# half-bridge.net
KiCad netlist of a schematic drawn in Altium Designer
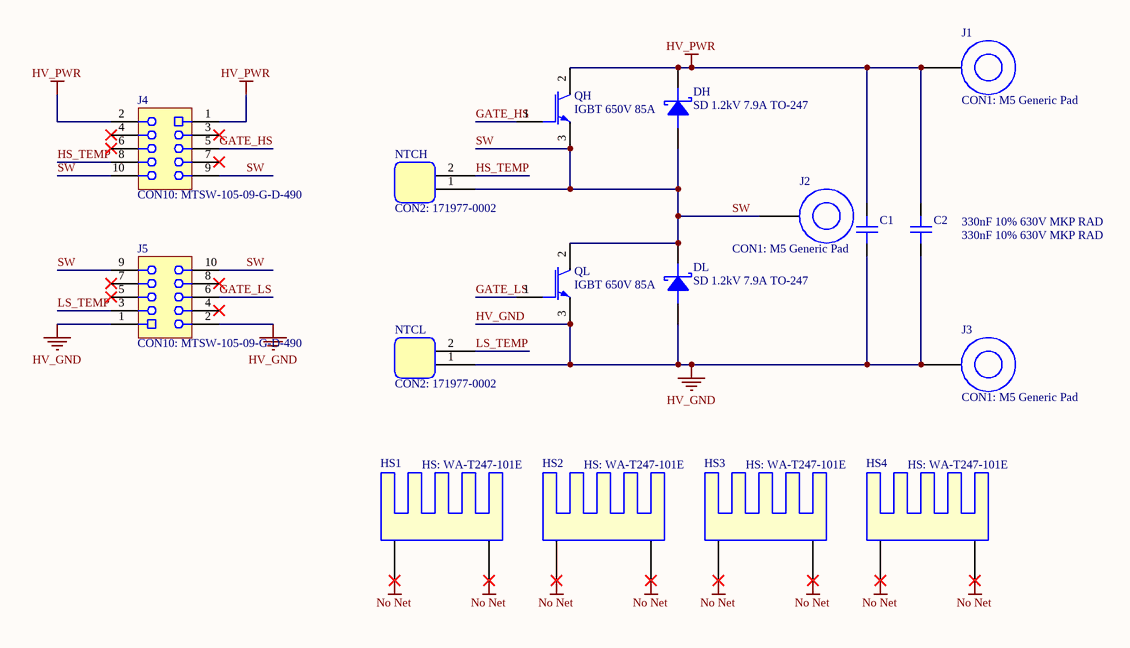
[diagram p0: half-bridge.SchDoc]

(export (version "E")
  (design (tool "Eeschema 10.0.6"))
  (components
    (comp (ref "C1")
      (value "330nF 10% 630V MKP RAD")
      (footprint "330nF 10% 630V MKP RAD-Footprint-1")
      (description "Film Capacitor, Polypropylene, 630V, 10% +Tol, 10% -Tol, 0.33uF, Through Hole Mount")
      (fields (field (name "MANUFACTURER PART NUMBER") "R71PI333050H6K"))
      (libsource (lib "EMEA- E-Tech Racing- I'Escola d'Enginyeria de Barcelona Est") (part "330nF 10% 630V MKP RAD"))
    )
    (comp (ref "C2")
      (value "330nF 10% 630V MKP RAD")
      (footprint "330nF 10% 630V MKP RAD-Footprint-1")
      (description "Film Capacitor, Polypropylene, 630V, 10% +Tol, 10% -Tol, 0.33uF, Through Hole Mount")
      (fields (field (name "MANUFACTURER PART NUMBER") "R71PI333050H6K"))
      (libsource (lib "EMEA- E-Tech Racing- I'Escola d'Enginyeria de Barcelona Est") (part "330nF 10% 630V MKP RAD"))
    )
    (comp (ref "DH")
      (value "SD 1.2kV 7.9A TO-247")
      (footprint "SSTO247-3-NCT")
      (description "L-series Gallium Oxide Schottky barrier diode from Novel Crystal Technology")
      (fields
        (field (name "MANUFACTURER PART NUMBER") "NCT-L")
        (field (name "MANUFACTURER") "Novel Crystal Technology")
      )
      (libsource (lib "EMEA- E-Tech Racing- I'Escola d'Enginyeria de Barcelona Est") (part "SD 1.2kV 7.9A TO-247"))
    )
    (comp (ref "DL")
      (value "SD 1.2kV 7.9A TO-247")
      (footprint "SSTO247-3-NCT")
      (description "L-series Gallium Oxide Schottky barrier diode from Novel Crystal Technology")
      (fields
        (field (name "MANUFACTURER PART NUMBER") "NCT-L")
        (field (name "MANUFACTURER") "Novel Crystal Technology")
      )
      (libsource (lib "EMEA- E-Tech Racing- I'Escola d'Enginyeria de Barcelona Est") (part "SD 1.2kV 7.9A TO-247"))
    )
    (comp (ref "HS1")
      (value "HS: WA-T247-101E")
      (footprint "FP-WA-T247-101E-MFG")
      (description "Heatsink, TEH100 Restr Series, TEH70 Restr Series, TO-247, 11C/W, 43.4X23.4X32MM")
      (fields (field (name "MANUFACTURER PART NUMBER") "WA-T247-101E"))
      (libsource (lib "EMEA- E-Tech Racing- I'Escola d'Enginyeria de Barcelona Est") (part "HS{colon}  OMNI-UNI-30-25-D-Symbol-1"))
    )
    (comp (ref "HS2")
      (value "HS: WA-T247-101E")
      (footprint "FP-WA-T247-101E-MFG")
      (description "Heatsink, TEH100 Restr Series, TEH70 Restr Series, TO-247, 11C/W, 43.4X23.4X32MM")
      (fields (field (name "MANUFACTURER PART NUMBER") "WA-T247-101E"))
      (libsource (lib "EMEA- E-Tech Racing- I'Escola d'Enginyeria de Barcelona Est") (part "HS{colon}  OMNI-UNI-30-25-D-Symbol-1"))
    )
    (comp (ref "HS3")
      (value "HS: WA-T247-101E")
      (footprint "FP-WA-T247-101E-MFG")
      (description "Heatsink, TEH100 Restr Series, TEH70 Restr Series, TO-247, 11C/W, 43.4X23.4X32MM")
      (fields (field (name "MANUFACTURER PART NUMBER") "WA-T247-101E"))
      (libsource (lib "EMEA- E-Tech Racing- I'Escola d'Enginyeria de Barcelona Est") (part "HS{colon}  OMNI-UNI-30-25-D-Symbol-1"))
    )
    (comp (ref "HS4")
      (value "HS: WA-T247-101E")
      (footprint "FP-WA-T247-101E-MFG")
      (description "Heatsink, TEH100 Restr Series, TEH70 Restr Series, TO-247, 11C/W, 43.4X23.4X32MM")
      (fields (field (name "MANUFACTURER PART NUMBER") "WA-T247-101E"))
      (libsource (lib "EMEA- E-Tech Racing- I'Escola d'Enginyeria de Barcelona Est") (part "HS{colon}  OMNI-UNI-30-25-D-Symbol-1"))
    )
    (comp (ref "J1")
      (value "CON1: M5 Generic Pad")
      (footprint "CON1: M5 Generic Pad-Footprint-1")
      (description "Generic M5 connector for power or mounting")
      (libsource (lib "EMEA- E-Tech Racing- I'Escola d'Enginyeria de Barcelona Est") (part "CON1{colon} M5 Generic Pad-Symbol-1"))
    )
    (comp (ref "J2")
      (value "CON1: M5 Generic Pad")
      (footprint "CON1: M5 Generic Pad-Footprint-1")
      (description "Generic M5 connector for power or mounting")
      (libsource (lib "EMEA- E-Tech Racing- I'Escola d'Enginyeria de Barcelona Est") (part "CON1{colon} M5 Generic Pad-Symbol-1"))
    )
    (comp (ref "J3")
      (value "CON1: M5 Generic Pad")
      (footprint "CON1: M5 Generic Pad-Footprint-1")
      (description "Generic M5 connector for power or mounting")
      (libsource (lib "EMEA- E-Tech Racing- I'Escola d'Enginyeria de Barcelona Est") (part "CON1{colon} M5 Generic Pad-Symbol-1"))
    )
    (comp (ref "J4")
      (value "CON10: MTSW-105-09-G-D-490")
      (footprint "MTSW-105-09-G-D-490")
      (description "Pin Header, Board-to-Board, 2.54 mm, 2 Rows, 10 Contacts, Through Hole, MTSW Series")
      (libsource (lib "EMEA- E-Tech Racing- I'Escola d'Enginyeria de Barcelona Est") (part "CN-2P-F-R10"))
    )
    (comp (ref "J5")
      (value "CON10: MTSW-105-09-G-D-490")
      (footprint "MTSW-105-09-G-D-490")
      (description "Pin Header, Board-to-Board, 2.54 mm, 2 Rows, 10 Contacts, Through Hole, MTSW Series")
      (libsource (lib "") (part "CN-2P-F-R10_1"))
    )
    (comp (ref "NTCH")
      (value "CON2: 171977-0002")
      (footprint "CON2: 171977-0002-Footprint-1")
      (fields (field (name "MANUFACTURER PART NUMBER") "171977-0002") (field (name "MANUFACTURER") "Molex"))
      (libsource (lib "EMEA- E-Tech Racing- I'Escola d'Enginyeria de Barcelona Est") (part "CON2{colon} 171977-0002-Symbol-1"))
    )
    (comp (ref "NTCL")
      (value "CON2: 171977-0002")
      (footprint "CON2: 171977-0002-Footprint-1")
      (fields (field (name "MANUFACTURER PART NUMBER") "171977-0002") (field (name "MANUFACTURER") "Molex"))
      (libsource (lib "EMEA- E-Tech Racing- I'Escola d'Enginyeria de Barcelona Est") (part "CON2{colon} 171977-0002-Symbol-1"))
    )
    (comp (ref "QH")
      (value "IGBT 650V 85A")
      (footprint "TO247P159X260-3")
      (description "650V, 85A, TO-247-3 Low VCE(sat) IGBT in TRENCHSTOP 5 technology")
      (fields
        (field (name "MANUFACTURER") "Infineon")
        (field (name "MANUFACTURER PART NUMBER") "IGW30N65L5XKSA1")
      )
      (libsource (lib "EMEA- E-Tech Racing- I'Escola d'Enginyeria de Barcelona Est") (part "IGBT 650V 85A"))
    )
    (comp (ref "QL")
      (value "IGBT 650V 85A")
      (footprint "TO247P159X260-3")
      (description "650V, 85A, TO-247-3 Low VCE(sat) IGBT in TRENCHSTOP 5 technology")
      (fields
        (field (name "MANUFACTURER") "Infineon")
        (field (name "MANUFACTURER PART NUMBER") "IGW30N65L5XKSA1")
      )
      (libsource (lib "EMEA- E-Tech Racing- I'Escola d'Enginyeria de Barcelona Est") (part "IGBT 650V 85A"))
    )
  )
  (nets
    (net (code "1") (name "/GATE_HS") (class "Default")
      (node (ref "J4") (pin "5") (pinfunction "5_5") (pintype "passive"))
      (node (ref "QH") (pin "1") (pinfunction "GATE_1") (pintype "passive"))
    )
    (net (code "2") (name "/GATE_LS") (class "Default")
      (node (ref "J5") (pin "6") (pinfunction "6_6") (pintype "passive"))
      (node (ref "QL") (pin "1") (pinfunction "GATE_1") (pintype "passive"))
    )
    (net (code "3") (name "/HS_TEMP") (class "Default")
      (node (ref "J4") (pin "8") (pinfunction "8_8") (pintype "passive"))
      (node (ref "NTCH") (pin "2") (pinfunction "2_2") (pintype "passive"))
    )
    (net (code "4") (name "/LS_TEMP") (class "Default")
      (node (ref "J5") (pin "3") (pinfunction "3_3") (pintype "passive"))
      (node (ref "NTCL") (pin "2") (pinfunction "2_2") (pintype "passive"))
    )
    (net (code "5") (name "/SW") (class "Default")
      (node (ref "DH") (pin "1") (pinfunction "A_1") (pintype "passive"))
      (node (ref "DL") (pin "2") (pinfunction "K_2") (pintype "passive"))
      (node (ref "DL") (pin "3") (pinfunction "K_3") (pintype "passive"))
      (node (ref "J2") (pin "1") (pinfunction "1_1") (pintype "passive"))
      (node (ref "J4") (pin "10") (pinfunction "10_10") (pintype "passive"))
      (node (ref "J4") (pin "9") (pinfunction "9_9") (pintype "passive"))
      (node (ref "J5") (pin "10") (pinfunction "10_10") (pintype "passive"))
      (node (ref "J5") (pin "9") (pinfunction "9_9") (pintype "passive"))
      (node (ref "NTCH") (pin "1") (pinfunction "1_1") (pintype "passive"))
      (node (ref "QH") (pin "3") (pinfunction "EMITTER_3") (pintype "passive"))
      (node (ref "QL") (pin "2") (pinfunction "COLLECTOR_2") (pintype "passive"))
    )
    (net (code "6") (name "HV_GND") (class "Default")
      (node (ref "C1") (pin "1") (pinfunction "1_1") (pintype "passive"))
      (node (ref "C2") (pin "1") (pinfunction "1_1") (pintype "passive"))
      (node (ref "DL") (pin "1") (pinfunction "A_1") (pintype "passive"))
      (node (ref "J3") (pin "1") (pinfunction "1_1") (pintype "passive"))
      (node (ref "J5") (pin "1") (pinfunction "1_1") (pintype "passive"))
      (node (ref "J5") (pin "2") (pinfunction "2_2") (pintype "passive"))
      (node (ref "NTCL") (pin "1") (pinfunction "1_1") (pintype "passive"))
      (node (ref "QL") (pin "3") (pinfunction "EMITTER_3") (pintype "passive"))
    )
    (net (code "7") (name "HV_PWR") (class "Default")
      (node (ref "C1") (pin "2") (pinfunction "2_2") (pintype "passive"))
      (node (ref "C2") (pin "2") (pinfunction "2_2") (pintype "passive"))
      (node (ref "DH") (pin "2") (pinfunction "K_2") (pintype "passive"))
      (node (ref "DH") (pin "3") (pinfunction "K_3") (pintype "passive"))
      (node (ref "J1") (pin "1") (pinfunction "1_1") (pintype "passive"))
      (node (ref "J4") (pin "1") (pinfunction "1_1") (pintype "passive"))
      (node (ref "J4") (pin "2") (pinfunction "2_2") (pintype "passive"))
      (node (ref "QH") (pin "2") (pinfunction "COLLECTOR_2") (pintype "passive"))
    )
    (net (code "8") (name "No Net") (class "Default")
      (node (ref "HS1") (pin "1") (pinfunction "1_1") (pintype "passive"))
      (node (ref "HS1") (pin "2") (pinfunction "2_2") (pintype "passive"))
      (node (ref "HS2") (pin "1") (pinfunction "1_1") (pintype "passive"))
      (node (ref "HS2") (pin "2") (pinfunction "2_2") (pintype "passive"))
      (node (ref "HS3") (pin "1") (pinfunction "1_1") (pintype "passive"))
      (node (ref "HS3") (pin "2") (pinfunction "2_2") (pintype "passive"))
      (node (ref "HS4") (pin "1") (pinfunction "1_1") (pintype "passive"))
      (node (ref "HS4") (pin "2") (pinfunction "2_2") (pintype "passive"))
    )
    (net (code "9") (name "unconnected-(J4-Pad3)") (class "Default")
      (node (ref "J4") (pin "3") (pinfunction "3_3") (pintype "passive+no_connect"))
    )
    (net (code "10") (name "unconnected-(J4-Pad4)") (class "Default")
      (node (ref "J4") (pin "4") (pinfunction "4_4") (pintype "passive+no_connect"))
    )
    (net (code "11") (name "unconnected-(J4-Pad6)") (class "Default")
      (node (ref "J4") (pin "6") (pinfunction "6_6") (pintype "passive+no_connect"))
    )
    (net (code "12") (name "unconnected-(J4-Pad7)") (class "Default")
      (node (ref "J4") (pin "7") (pinfunction "7_7") (pintype "passive+no_connect"))
    )
    (net (code "13") (name "unconnected-(J5-Pad4)") (class "Default")
      (node (ref "J5") (pin "4") (pinfunction "4_4") (pintype "passive+no_connect"))
    )
    (net (code "14") (name "unconnected-(J5-Pad5)") (class "Default")
      (node (ref "J5") (pin "5") (pinfunction "5_5") (pintype "passive+no_connect"))
    )
    (net (code "15") (name "unconnected-(J5-Pad7)") (class "Default")
      (node (ref "J5") (pin "7") (pinfunction "7_7") (pintype "passive+no_connect"))
    )
    (net (code "16") (name "unconnected-(J5-Pad8)") (class "Default")
      (node (ref "J5") (pin "8") (pinfunction "8_8") (pintype "passive+no_connect"))
    )
  )
)
